# mimosa_simple_button.net
KiCad netlist of a schematic drawn in Altium Designer
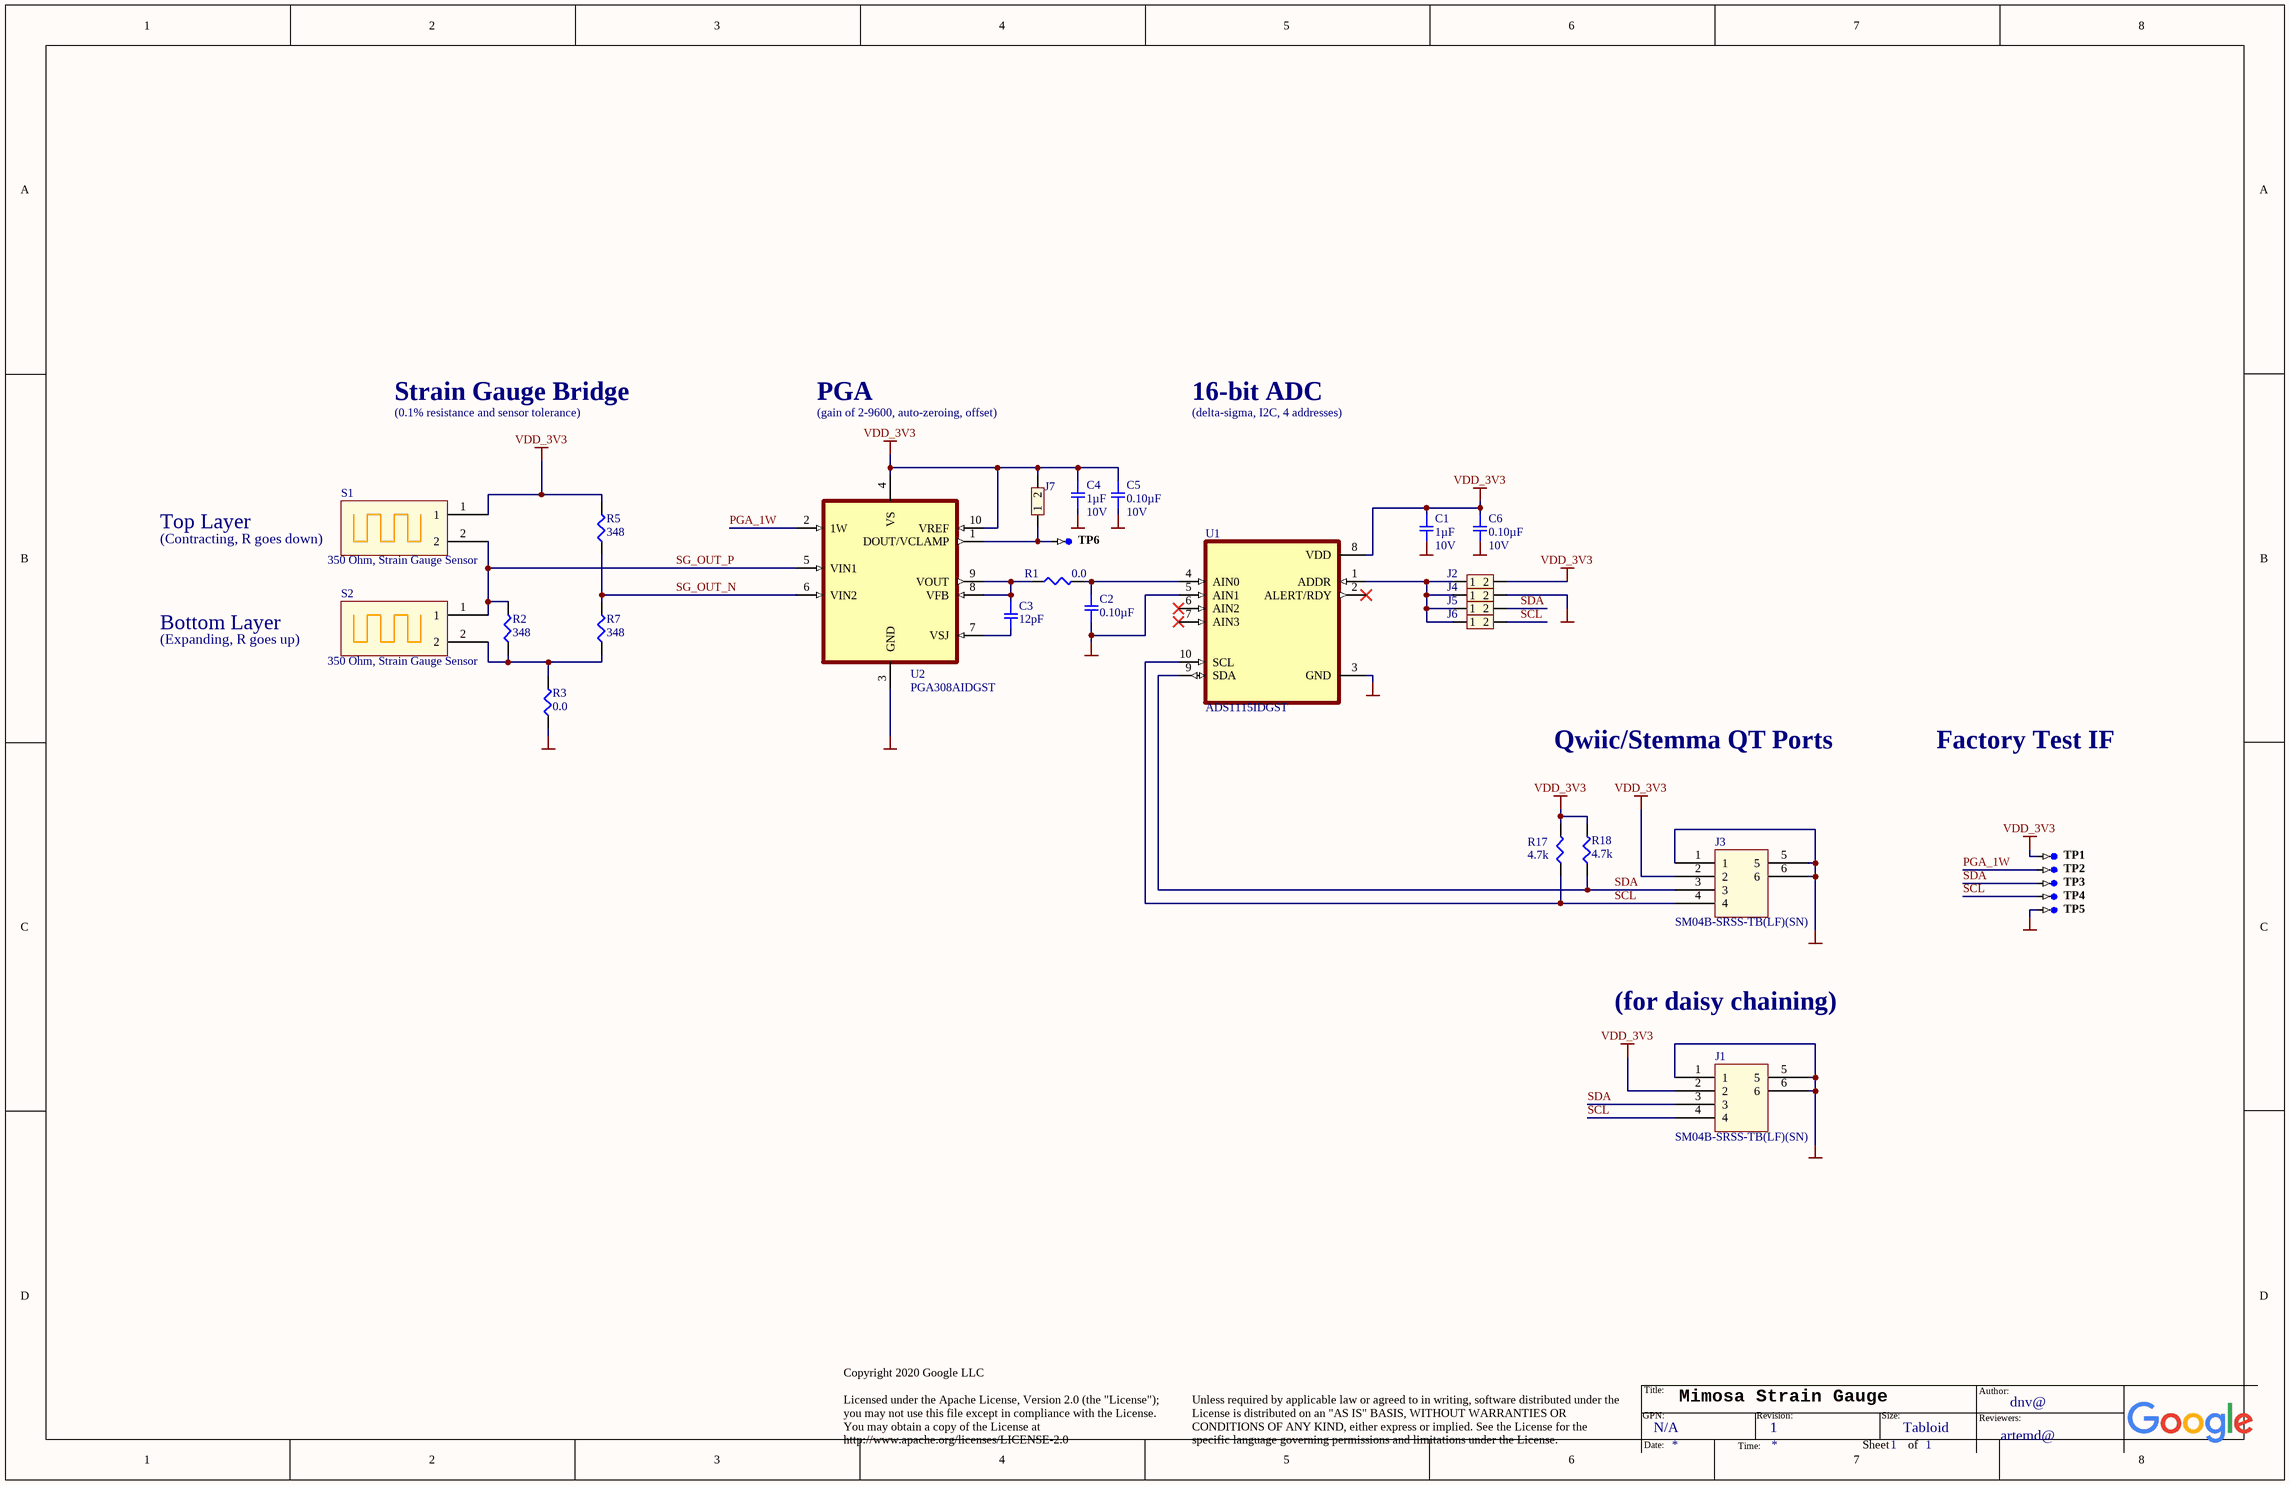
[diagram p0: mimosa_simple_button.SchDoc]

(export (version "E")
  (design (tool "Eeschema 10.0.6"))
  (components
    (comp (ref "C1")
      (value "1µF")
      (footprint "SMD-0402C")
      (description "CAP CER 1UF 10V X5R 0402")
      (fields
        (field (name "DIGI-KEY PART NUMBER") "490-3890-1-ND")
        (field (name "PART NUMBER") "GRM155R61A105KE15D")
        (field (name "VOLTAGE") "10V")
      )
      (libsource (lib "cap_murata_0402") (part "GRM155R61A105KE15D"))
    )
    (comp (ref "C2")
      (value "0.10µF")
      (footprint "SMD-0402C")
      (description "CAP CER 0.1UF 16V X7R 0402")
      (fields
        (field (name "DIGI-KEY PART NUMBER") "490-4759-1-ND")
        (field (name "PART NUMBER") "GCM155R71C104KA55D")
      )
      (libsource (lib "cap_murata_0402") (part "GCM155R71C104KA55D"))
    )
    (comp (ref "C3")
      (value "12pF")
      (footprint "SMD-0402C")
      (description "CAP CER 12PF 50V NP0 0402")
      (fields
        (field (name "DIGI-KEY PART NUMBER") "490-12649-1-ND")
        (field (name "PART NUMBER") "GCM1555C1H120JA16D")
      )
      (libsource (lib "cap_murata_0402") (part "GCM1555C1H120JA16D"))
    )
    (comp (ref "C4")
      (value "1µF")
      (footprint "SMD-0402C")
      (description "CAP CER 1UF 10V X5R 0402")
      (fields
        (field (name "DIGI-KEY PART NUMBER") "490-3890-1-ND")
        (field (name "PART NUMBER") "GRM155R61A105KE15D")
        (field (name "VOLTAGE") "10V")
      )
      (libsource (lib "cap_murata_0402") (part "GRM155R61A105KE15D"))
    )
    (comp (ref "C5")
      (value "0.10µF")
      (footprint "SMD-0402C")
      (description "CAP CER 0.1UF 10V X5R 0402")
      (fields
        (field (name "DIGI-KEY PART NUMBER") "490-10008-1-ND")
        (field (name "PART NUMBER") "GRM152R61A104KE19D")
        (field (name "VOLTAGE") "10V")
      )
      (libsource (lib "cap_murata_0402") (part "GRM152R61A104KE19D"))
    )
    (comp (ref "C6")
      (value "0.10µF")
      (footprint "SMD-0402C")
      (description "CAP CER 0.1UF 10V X5R 0402")
      (fields
        (field (name "DIGI-KEY PART NUMBER") "490-10008-1-ND")
        (field (name "PART NUMBER") "GRM152R61A104KE19D")
        (field (name "VOLTAGE") "10V")
      )
      (libsource (lib "cap_murata_0402") (part "GRM152R61A104KE19D"))
    )
    (comp (ref "J1")
      (value "SM04B-SRSS-TB(LF)(SN)")
      (footprint "JST-SH:4208")
      (libsource (lib "JST-SH") (part "4208"))
    )
    (comp (ref "J2")
      (value "solder bridge jumper, open")
      (footprint "JUMPER1P5MMX1P5MM_OPEN")
      (libsource (lib "") (part "jumper_open_1"))
    )
    (comp (ref "J3")
      (value "SM04B-SRSS-TB(LF)(SN)")
      (footprint "JST-SH:4208")
      (libsource (lib "JST-SH") (part "4208"))
    )
    (comp (ref "J4")
      (value "solder bridge jumper, open")
      (footprint "JUMPER1P5MMX1P5MM_OPEN")
      (libsource (lib "") (part "jumper_open_1"))
    )
    (comp (ref "J5")
      (value "solder bridge jumper, open")
      (footprint "JUMPER1P5MMX1P5MM_OPEN")
      (libsource (lib "") (part "jumper_open_1"))
    )
    (comp (ref "J6")
      (value "solder bridge jumper, open")
      (footprint "JUMPER1P5MMX1P5MM_OPEN")
      (libsource (lib "") (part "jumper_open_1"))
    )
    (comp (ref "J7")
      (value "solder bridge jumper, open")
      (footprint "JUMPER1P5MMX1P5MM_OPEN")
      (libsource (lib "Jumpers") (part "jumper_open"))
    )
    (comp (ref "R1")
      (value "0.0")
      (footprint "SMD-0402-RES")
      (description "RES SMD 0.0OHM JUMPER 1/10W 0402")
      (fields (field (name "PART NUMBER") "ERJ-2GE0R00X") (field (name "DIGI-KEY PART NUMBER") "P0.0JCT-ND"))
      (libsource (lib "res_0402_panasonic_ERJ") (part "ERJ-2GE0R00X"))
    )
    (comp (ref "R2")
      (value "348")
      (footprint "SMD-0402-RES")
      (description "RES SMD 348 OHM 1% 1/10W 0402")
      (fields (field (name "PART NUMBER") "ERJ-2RKF3480X") (field (name "DIGI-KEY PART NUMBER") "P348LCT-ND"))
      (libsource (lib "res_0402_panasonic_ERJ") (part "ERJ-2RKF3480X"))
    )
    (comp (ref "R3")
      (value "0.0")
      (footprint "SMD-0402-RES")
      (description "RES SMD 0.0OHM JUMPER 1/10W 0402")
      (fields (field (name "PART NUMBER") "ERJ-2GE0R00X") (field (name "DIGI-KEY PART NUMBER") "P0.0JCT-ND"))
      (libsource (lib "res_0402_panasonic_ERJ") (part "ERJ-2GE0R00X"))
    )
    (comp (ref "R5")
      (value "348")
      (footprint "SMD-0402-RES")
      (description "RES SMD 348 OHM 1% 1/10W 0402")
      (fields (field (name "PART NUMBER") "ERJ-2RKF3480X") (field (name "DIGI-KEY PART NUMBER") "P348LCT-ND"))
      (libsource (lib "res_0402_panasonic_ERJ") (part "ERJ-2RKF3480X"))
    )
    (comp (ref "R7")
      (value "348")
      (footprint "SMD-0402-RES")
      (description "RES SMD 348 OHM 1% 1/10W 0402")
      (fields (field (name "PART NUMBER") "ERJ-2RKF3480X") (field (name "DIGI-KEY PART NUMBER") "P348LCT-ND"))
      (libsource (lib "res_0402_panasonic_ERJ") (part "ERJ-2RKF3480X"))
    )
    (comp (ref "R17")
      (value "4.7k")
      (footprint "SMD-0402-RES")
      (description "RES SMD 4.7K OHM 5% 1/10W 0402")
      (fields (field (name "PART NUMBER") "ERJ-2GEJ472X") (field (name "DIGI-KEY PART NUMBER") "P4.7KJCT-ND"))
      (libsource (lib "res_0402_panasonic_ERJ") (part "ERJ-2GEJ472X"))
    )
    (comp (ref "R18")
      (value "4.7k")
      (footprint "SMD-0402-RES")
      (description "RES SMD 4.7K OHM 5% 1/10W 0402")
      (fields (field (name "PART NUMBER") "ERJ-2GEJ472X") (field (name "DIGI-KEY PART NUMBER") "P4.7KJCT-ND"))
      (libsource (lib "res_0402_panasonic_ERJ") (part "ERJ-2GEJ472X"))
    )
    (comp (ref "S1")
      (value "350 Ohm, Strain Gauge Sensor")
      (footprint "Strain_Gauge:BF350-3AA-NARROW")
      (libsource (lib "Strain_Gauge") (part "BF350-3AA"))
    )
    (comp (ref "S2")
      (value "350 Ohm, Strain Gauge Sensor")
      (footprint "Strain_Gauge:BF350-3AA-NARROW")
      (libsource (lib "Strain_Gauge") (part "BF350-3AA"))
    )
    (comp (ref "TP1")
      (value "TP-SM-C-100")
      (footprint "TP-SM-C-100")
      (description "Test Point, Surface Mount, Circular, Pad Diameter 1 mm")
      (fields (field (name "MANUFACTURER") "No Vendor"))
      (libsource (lib "Sky32") (part "CMP-0484-00002-2"))
    )
    (comp (ref "TP2")
      (value "TP-SM-C-100")
      (footprint "TP-SM-C-100")
      (description "Test Point, Surface Mount, Circular, Pad Diameter 1 mm")
      (fields (field (name "MANUFACTURER") "No Vendor"))
      (libsource (lib "Sky32") (part "CMP-0484-00002-2"))
    )
    (comp (ref "TP3")
      (value "TP-SM-C-100")
      (footprint "TP-SM-C-100")
      (description "Test Point, Surface Mount, Circular, Pad Diameter 1 mm")
      (fields (field (name "MANUFACTURER") "No Vendor"))
      (libsource (lib "Sky32") (part "CMP-0484-00002-2"))
    )
    (comp (ref "TP4")
      (value "TP-SM-C-100")
      (footprint "TP-SM-C-100")
      (description "Test Point, Surface Mount, Circular, Pad Diameter 1 mm")
      (fields (field (name "MANUFACTURER") "No Vendor"))
      (libsource (lib "Sky32") (part "CMP-0484-00002-2"))
    )
    (comp (ref "TP5")
      (value "TP-SM-C-100")
      (footprint "TP-SM-C-100")
      (description "Test Point, Surface Mount, Circular, Pad Diameter 1 mm")
      (fields (field (name "MANUFACTURER") "No Vendor"))
      (libsource (lib "Sky32") (part "CMP-0484-00002-2"))
    )
    (comp (ref "TP6")
      (value "TP-SM-C-100")
      (footprint "TP-SM-C-100")
      (description "Test Point, Surface Mount, Circular, Pad Diameter 1 mm")
      (fields (field (name "MANUFACTURER") "No Vendor"))
      (libsource (lib "Sky32") (part "CMP-0484-00002-2"))
    )
    (comp (ref "U1")
      (value "ADS1115IDGST")
      (footprint "SOP50P490X110_10N:SOP50P490X110-10N")
      (fields (field (name "MP") "ADS1015IDGST") (field (name "MF") "Texas Instruments"))
      (libsource (lib "ADS1015IDGST") (part "ADS1015IDGST"))
    )
    (comp (ref "U2")
      (value "PGA308AIDGST")
      (footprint "SOP50P490X110_10N:SOP50P490X110-10N")
      (libsource (lib "PGA308AIDGST") (part "PGA308AIDGST"))
    )
  )
  (nets
    (net (code "1") (name "/PGA_1W") (class "Default")
      (node (ref "TP2") (pin "1") (pinfunction "1_1") (pintype "input"))
      (node (ref "U2") (pin "2") (pinfunction "1W_2") (pintype "input"))
    )
    (net (code "2") (name "/SCL") (class "Default")
      (node (ref "J1") (pin "4") (pinfunction "4_4") (pintype "passive"))
      (node (ref "J3") (pin "4") (pinfunction "4_4") (pintype "passive"))
      (node (ref "J6") (pin "2") (pinfunction "2_2") (pintype "passive"))
      (node (ref "R17") (pin "1") (pinfunction "1_1") (pintype "passive"))
      (node (ref "TP4") (pin "1") (pinfunction "1_1") (pintype "input"))
      (node (ref "U1") (pin "10") (pinfunction "SCL_10") (pintype "input"))
    )
    (net (code "3") (name "/SDA") (class "Default")
      (node (ref "J1") (pin "3") (pinfunction "3_3") (pintype "passive"))
      (node (ref "J3") (pin "3") (pinfunction "3_3") (pintype "passive"))
      (node (ref "J5") (pin "2") (pinfunction "2_2") (pintype "passive"))
      (node (ref "R18") (pin "1") (pinfunction "1_1") (pintype "passive"))
      (node (ref "TP3") (pin "1") (pinfunction "1_1") (pintype "input"))
      (node (ref "U1") (pin "9") (pinfunction "SDA_9") (pintype "bidirectional"))
    )
    (net (code "4") (name "/SG_OUT_N") (class "Default")
      (node (ref "R5") (pin "1") (pinfunction "1_1") (pintype "passive"))
      (node (ref "R7") (pin "2") (pinfunction "2_2") (pintype "passive"))
      (node (ref "U2") (pin "6") (pinfunction "VIN2_6") (pintype "input"))
    )
    (net (code "5") (name "/SG_OUT_P") (class "Default")
      (node (ref "R2") (pin "2") (pinfunction "2_2") (pintype "passive"))
      (node (ref "S1") (pin "2") (pinfunction "2_2") (pintype "passive"))
      (node (ref "S2") (pin "1") (pinfunction "1_1") (pintype "passive"))
      (node (ref "U2") (pin "5") (pinfunction "VIN1_5") (pintype "input"))
    )
    (net (code "6") (name "GND") (class "Default")
      (node (ref "C1") (pin "2") (pinfunction "2_2") (pintype "passive"))
      (node (ref "C2") (pin "1") (pinfunction "1_1") (pintype "passive"))
      (node (ref "C4") (pin "2") (pinfunction "2_2") (pintype "passive"))
      (node (ref "C5") (pin "2") (pinfunction "2_2") (pintype "passive"))
      (node (ref "C6") (pin "2") (pinfunction "2_2") (pintype "passive"))
      (node (ref "J1") (pin "1") (pinfunction "1_1") (pintype "passive"))
      (node (ref "J1") (pin "5") (pinfunction "5_5") (pintype "passive"))
      (node (ref "J1") (pin "6") (pinfunction "6_6") (pintype "passive"))
      (node (ref "J3") (pin "1") (pinfunction "1_1") (pintype "passive"))
      (node (ref "J3") (pin "5") (pinfunction "5_5") (pintype "passive"))
      (node (ref "J3") (pin "6") (pinfunction "6_6") (pintype "passive"))
      (node (ref "J4") (pin "2") (pinfunction "2_2") (pintype "passive"))
      (node (ref "R3") (pin "1") (pinfunction "1_1") (pintype "passive"))
      (node (ref "TP5") (pin "1") (pinfunction "1_1") (pintype "input"))
      (node (ref "U1") (pin "3") (pinfunction "GND_3") (pintype "power_in"))
      (node (ref "U1") (pin "5") (pinfunction "AIN1_5") (pintype "input"))
      (node (ref "U2") (pin "3") (pinfunction "GND_3") (pintype "power_in"))
    )
    (net (code "7") (name "Net-(R2-Pad1)") (class "Default")
      (node (ref "R2") (pin "1") (pinfunction "1_1") (pintype "passive"))
      (node (ref "R3") (pin "2") (pinfunction "2_2") (pintype "passive"))
      (node (ref "R7") (pin "1") (pinfunction "1_1") (pintype "passive"))
      (node (ref "S2") (pin "2") (pinfunction "2_2") (pintype "passive"))
    )
    (net (code "8") (name "Net-(U1-ADDR)") (class "Default")
      (node (ref "J2") (pin "1") (pinfunction "1_1") (pintype "passive"))
      (node (ref "J4") (pin "1") (pinfunction "1_1") (pintype "passive"))
      (node (ref "J5") (pin "1") (pinfunction "1_1") (pintype "passive"))
      (node (ref "J6") (pin "1") (pinfunction "1_1") (pintype "passive"))
      (node (ref "U1") (pin "1") (pinfunction "ADDR_1") (pintype "input"))
    )
    (net (code "9") (name "Net-(U1-AIN0)") (class "Default")
      (node (ref "C2") (pin "2") (pinfunction "2_2") (pintype "passive"))
      (node (ref "R1") (pin "2") (pinfunction "2_2") (pintype "passive"))
      (node (ref "U1") (pin "4") (pinfunction "AIN0_4") (pintype "input"))
    )
    (net (code "10") (name "Net-(U2-DOUT{slash}VCLAMP)") (class "Default")
      (node (ref "J7") (pin "1") (pinfunction "1_1") (pintype "passive"))
      (node (ref "TP6") (pin "1") (pinfunction "1_1") (pintype "input"))
      (node (ref "U2") (pin "1") (pinfunction "DOUT/VCLAMP_1") (pintype "output"))
    )
    (net (code "11") (name "Net-(U2-VFB)") (class "Default")
      (node (ref "C3") (pin "1") (pinfunction "1_1") (pintype "passive"))
      (node (ref "R1") (pin "1") (pinfunction "1_1") (pintype "passive"))
      (node (ref "U2") (pin "8") (pinfunction "VFB_8") (pintype "input"))
      (node (ref "U2") (pin "9") (pinfunction "VOUT_9") (pintype "output"))
    )
    (net (code "12") (name "Net-(U2-VSJ)") (class "Default")
      (node (ref "C3") (pin "2") (pinfunction "2_2") (pintype "passive"))
      (node (ref "U2") (pin "7") (pinfunction "VSJ_7") (pintype "input"))
    )
    (net (code "13") (name "VDD_3V3") (class "Default")
      (node (ref "C1") (pin "1") (pinfunction "1_1") (pintype "passive"))
      (node (ref "C4") (pin "1") (pinfunction "1_1") (pintype "passive"))
      (node (ref "C5") (pin "1") (pinfunction "1_1") (pintype "passive"))
      (node (ref "C6") (pin "1") (pinfunction "1_1") (pintype "passive"))
      (node (ref "J1") (pin "2") (pinfunction "2_2") (pintype "passive"))
      (node (ref "J2") (pin "2") (pinfunction "2_2") (pintype "passive"))
      (node (ref "J3") (pin "2") (pinfunction "2_2") (pintype "passive"))
      (node (ref "J7") (pin "2") (pinfunction "2_2") (pintype "passive"))
      (node (ref "R17") (pin "2") (pinfunction "2_2") (pintype "passive"))
      (node (ref "R18") (pin "2") (pinfunction "2_2") (pintype "passive"))
      (node (ref "R5") (pin "2") (pinfunction "2_2") (pintype "passive"))
      (node (ref "S1") (pin "1") (pinfunction "1_1") (pintype "passive"))
      (node (ref "TP1") (pin "1") (pinfunction "1_1") (pintype "input"))
      (node (ref "U1") (pin "8") (pinfunction "VDD_8") (pintype "power_in"))
      (node (ref "U2") (pin "10") (pinfunction "VREF_10") (pintype "input"))
      (node (ref "U2") (pin "4") (pinfunction "VS_4") (pintype "power_in"))
    )
    (net (code "14") (name "unconnected-(U1-AIN2-Pad6)") (class "Default")
      (node (ref "U1") (pin "6") (pinfunction "AIN2_6") (pintype "input+no_connect"))
    )
    (net (code "15") (name "unconnected-(U1-AIN3-Pad7)") (class "Default")
      (node (ref "U1") (pin "7") (pinfunction "AIN3_7") (pintype "input+no_connect"))
    )
    (net (code "16") (name "unconnected-(U1-ALERT{slash}RDY-Pad2)") (class "Default")
      (node (ref "U1") (pin "2") (pinfunction "ALERT/RDY_2") (pintype "output+no_connect"))
    )
  )
)
